# 3_CAN.net
KiCad netlist of a schematic drawn in Altium Designer
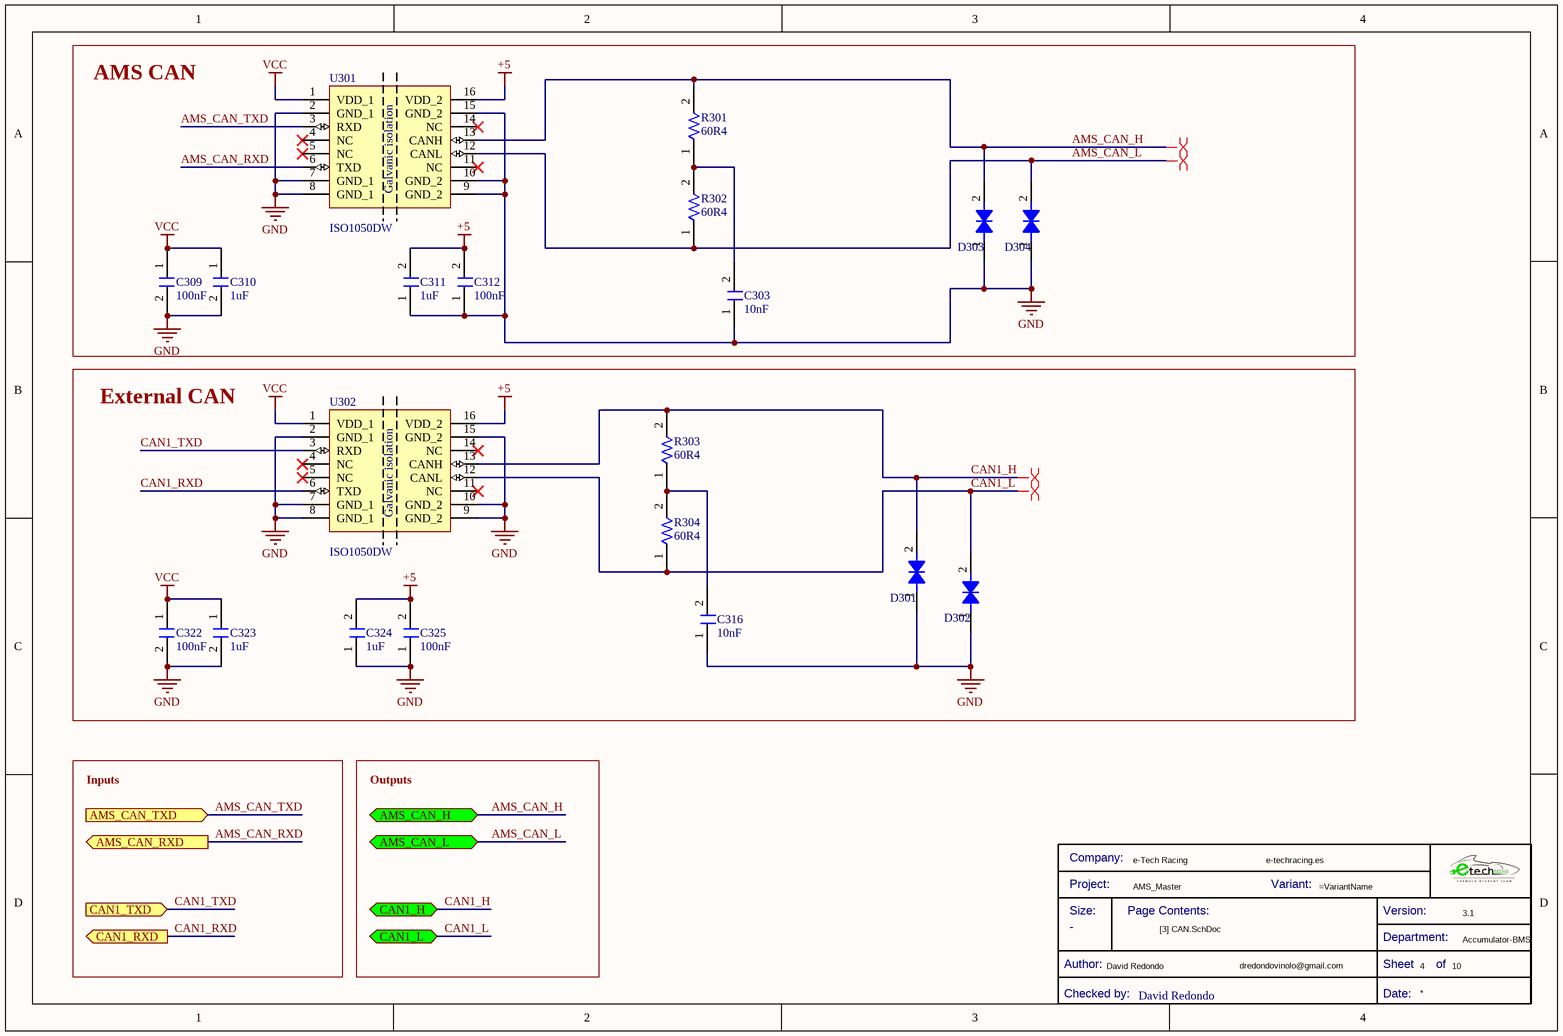
[diagram p0: [3] CAN.SchDoc]

(export (version "E")
  (design (tool "Eeschema 10.0.6"))
  (components
    (comp (ref "C303")
      (value "885012207092")
      (footprint "C0805FNPC-R")
      (description "Cap, 0.01ΜF, 50V, 10%, X7R, 0805")
      (fields
        (field (name "TOLERANCE") "10%")
        (field (name "CAPACITANCE") "10nF")
        (field (name ".CREATOR") "DR")
      )
      (libsource (lib "Passives") (part "C10n-50V-0805FNPC-X7R"))
    )
    (comp (ref "C309")
      (value "885012207098")
      (footprint "C0805FNPC-R")
      (description "Cap, 0.1ΜF, 50V, 10%, X7R, 0805")
      (fields
        (field (name "TOLERANCE") "10%")
        (field (name "CAPACITANCE") "100nF")
        (field (name ".CREATOR") "DR")
      )
      (libsource (lib "Passives") (part "C100n-50V-0805FNPC-X7R"))
    )
    (comp (ref "C310")
      (value "885012207103")
      (footprint "C0805FNPC-R")
      (fields
        (field (name "TOLERANCE") "10%")
        (field (name "CAPACITANCE") "1uF")
        (field (name ".CREATOR") "GP")
      )
      (libsource (lib "Passives") (part "C1u-50V-0805FNPC-X7R"))
    )
    (comp (ref "C311")
      (value "885012207103")
      (footprint "C0805FNPC-R")
      (fields
        (field (name "TOLERANCE") "10%")
        (field (name "CAPACITANCE") "1uF")
        (field (name ".CREATOR") "GP")
      )
      (libsource (lib "Passives") (part "C1u-50V-0805FNPC-X7R"))
    )
    (comp (ref "C312")
      (value "885012207098")
      (footprint "C0805FNPC-R")
      (description "Cap, 0.1ΜF, 50V, 10%, X7R, 0805")
      (fields
        (field (name "TOLERANCE") "10%")
        (field (name "CAPACITANCE") "100nF")
        (field (name ".CREATOR") "DR")
      )
      (libsource (lib "Passives") (part "C100n-50V-0805FNPC-X7R"))
    )
    (comp (ref "C316")
      (value "885012207092")
      (footprint "C0805FNPC-R")
      (description "Cap, 0.01ΜF, 50V, 10%, X7R, 0805")
      (fields
        (field (name "TOLERANCE") "10%")
        (field (name "CAPACITANCE") "10nF")
        (field (name ".CREATOR") "DR")
      )
      (libsource (lib "Passives") (part "C10n-50V-0805FNPC-X7R"))
    )
    (comp (ref "C322")
      (value "885012207098")
      (footprint "C0805FNPC-R")
      (description "Cap, 0.1ΜF, 50V, 10%, X7R, 0805")
      (fields
        (field (name "TOLERANCE") "10%")
        (field (name "CAPACITANCE") "100nF")
        (field (name ".CREATOR") "DR")
      )
      (libsource (lib "Passives") (part "C100n-50V-0805FNPC-X7R"))
    )
    (comp (ref "C323")
      (value "885012207103")
      (footprint "C0805FNPC-R")
      (fields
        (field (name "TOLERANCE") "10%")
        (field (name "CAPACITANCE") "1uF")
        (field (name ".CREATOR") "GP")
      )
      (libsource (lib "Passives") (part "C1u-50V-0805FNPC-X7R"))
    )
    (comp (ref "C324")
      (value "885012207103")
      (footprint "C0805FNPC-R")
      (fields
        (field (name "TOLERANCE") "10%")
        (field (name "CAPACITANCE") "1uF")
        (field (name ".CREATOR") "GP")
      )
      (libsource (lib "Passives") (part "C1u-50V-0805FNPC-X7R"))
    )
    (comp (ref "C325")
      (value "885012207098")
      (footprint "C0805FNPC-R")
      (description "Cap, 0.1ΜF, 50V, 10%, X7R, 0805")
      (fields
        (field (name "TOLERANCE") "10%")
        (field (name "CAPACITANCE") "100nF")
        (field (name ".CREATOR") "DR")
      )
      (libsource (lib "Passives") (part "C100n-50V-0805FNPC-X7R"))
    )
    (comp (ref "D301")
      (value "824501600")
      (footprint "DTVS-DO-214AC")
      (description "TVS diode [Würth Elektronik] 824501600 TVS diode")
      (fields (field (name "MANUFACTURER") "Wurth Electronics") (field (name ".CREATOR") "DO"))
      (libsource (lib "Filter components") (part "DTVS-6V-DO-214AC"))
    )
    (comp (ref "D302")
      (value "824501600")
      (footprint "DTVS-DO-214AC")
      (description "TVS diode [Würth Elektronik] 824501600 TVS diode")
      (fields (field (name "MANUFACTURER") "Wurth Electronics") (field (name ".CREATOR") "DO"))
      (libsource (lib "Filter components") (part "DTVS-6V-DO-214AC"))
    )
    (comp (ref "D303")
      (value "824501600")
      (footprint "DTVS-DO-214AC")
      (description "TVS diode [Würth Elektronik] 824501600 TVS diode")
      (fields (field (name "MANUFACTURER") "Wurth Electronics") (field (name ".CREATOR") "DO"))
      (libsource (lib "Filter components") (part "DTVS-6V-DO-214AC"))
    )
    (comp (ref "D304")
      (value "824501600")
      (footprint "DTVS-DO-214AC")
      (description "TVS diode [Würth Elektronik] 824501600 TVS diode")
      (fields (field (name "MANUFACTURER") "Wurth Electronics") (field (name ".CREATOR") "DO"))
      (libsource (lib "Filter components") (part "DTVS-6V-DO-214AC"))
    )
    (comp (ref "R301")
      (value "60R4")
      (footprint "R0805FTK")
      (description "Res Thin Film 0805 60.4 Ohm 0.1% 1/8W ±25ppm/°C Molded SMD SMD Punched Carrier T/R")
      (fields
        (field (name "TOLERANCE") "0.1%")
        (field (name "Comment") "R60-0805FTN")
        (field (name ".CREATOR") "DR")
      )
      (libsource (lib "Passives") (part "R60-0805FTN"))
    )
    (comp (ref "R302")
      (value "60R4")
      (footprint "R0805FTK")
      (description "Res Thin Film 0805 60.4 Ohm 0.1% 1/8W ±25ppm/°C Molded SMD SMD Punched Carrier T/R")
      (fields
        (field (name "TOLERANCE") "0.1%")
        (field (name "Comment") "R60-0805FTN")
        (field (name ".CREATOR") "DR")
      )
      (libsource (lib "Passives") (part "R60-0805FTN"))
    )
    (comp (ref "R303")
      (value "60R4")
      (footprint "R0805FTK")
      (description "Res Thin Film 0805 60.4 Ohm 0.1% 1/8W ±25ppm/°C Molded SMD SMD Punched Carrier T/R")
      (fields
        (field (name "TOLERANCE") "0.1%")
        (field (name "Comment") "R60-0805FTN")
        (field (name ".CREATOR") "DR")
      )
      (libsource (lib "Passives") (part "R60-0805FTN"))
    )
    (comp (ref "R304")
      (value "60R4")
      (footprint "R0805FTK")
      (description "Res Thin Film 0805 60.4 Ohm 0.1% 1/8W ±25ppm/°C Molded SMD SMD Punched Carrier T/R")
      (fields
        (field (name "TOLERANCE") "0.1%")
        (field (name "Comment") "R60-0805FTN")
        (field (name ".CREATOR") "DR")
      )
      (libsource (lib "Passives") (part "R60-0805FTN"))
    )
    (comp (ref "U301")
      (value "ISO1050DW")
      (footprint "TRANSCEIVER_CAN_SOIC16")
      (description "Isolated 5-V CAN transceiver 16-SOIC -55 to 105")
      (fields (field (name "SUPPLIER PART NUMBER 1") "ISO1050DW") (field (name ".CREATOR") "DR"))
      (libsource (lib "Integrated circuits") (part "Transceiver_CAN_ISO1050"))
    )
    (comp (ref "U302")
      (value "ISO1050DW")
      (footprint "TRANSCEIVER_CAN_SOIC16")
      (description "Isolated 5-V CAN transceiver 16-SOIC -55 to 105")
      (fields (field (name "SUPPLIER PART NUMBER 1") "ISO1050DW") (field (name ".CREATOR") "DR"))
      (libsource (lib "Integrated circuits") (part "Transceiver_CAN_ISO1050"))
    )
  )
  (nets
    (net (code "1") (name "+5") (class "Default")
      (node (ref "C311") (pin "2") (pinfunction "2_2") (pintype "passive"))
      (node (ref "C312") (pin "2") (pinfunction "2_2") (pintype "passive"))
      (node (ref "C324") (pin "2") (pinfunction "2_2") (pintype "passive"))
      (node (ref "C325") (pin "2") (pinfunction "2_2") (pintype "passive"))
      (node (ref "U301") (pin "16") (pinfunction "VDD_2_16") (pintype "passive"))
      (node (ref "U302") (pin "16") (pinfunction "VDD_2_16") (pintype "passive"))
    )
    (net (code "2") (name "/AMS_CAN_H") (class "Default")
      (node (ref "D303") (pin "2") (pinfunction "2_2") (pintype "passive"))
      (node (ref "R301") (pin "2") (pinfunction "2_2") (pintype "passive"))
      (node (ref "U301") (pin "13") (pinfunction "CANH_13") (pintype "bidirectional"))
    )
    (net (code "3") (name "/AMS_CAN_L") (class "Default")
      (node (ref "D304") (pin "2") (pinfunction "2_2") (pintype "passive"))
      (node (ref "R302") (pin "1") (pinfunction "1_1") (pintype "passive"))
      (node (ref "U301") (pin "12") (pinfunction "CANL_12") (pintype "bidirectional"))
    )
    (net (code "4") (name "/AMS_CAN_RXD") (class "Default")
      (node (ref "U301") (pin "6") (pinfunction "TXD_6") (pintype "bidirectional"))
    )
    (net (code "5") (name "/AMS_CAN_TXD") (class "Default")
      (node (ref "U301") (pin "3") (pinfunction "RXD_3") (pintype "bidirectional"))
    )
    (net (code "6") (name "/CAN1_H") (class "Default")
      (node (ref "D301") (pin "2") (pinfunction "2_2") (pintype "passive"))
      (node (ref "R303") (pin "2") (pinfunction "2_2") (pintype "passive"))
      (node (ref "U302") (pin "13") (pinfunction "CANH_13") (pintype "bidirectional"))
    )
    (net (code "7") (name "/CAN1_L") (class "Default")
      (node (ref "D302") (pin "2") (pinfunction "2_2") (pintype "passive"))
      (node (ref "R304") (pin "1") (pinfunction "1_1") (pintype "passive"))
      (node (ref "U302") (pin "12") (pinfunction "CANL_12") (pintype "bidirectional"))
    )
    (net (code "8") (name "/CAN1_RXD") (class "Default")
      (node (ref "U302") (pin "6") (pinfunction "TXD_6") (pintype "bidirectional"))
    )
    (net (code "9") (name "/CAN1_TXD") (class "Default")
      (node (ref "U302") (pin "3") (pinfunction "RXD_3") (pintype "bidirectional"))
    )
    (net (code "10") (name "GND") (class "Default")
      (node (ref "C303") (pin "1") (pinfunction "1_1") (pintype "passive"))
      (node (ref "C309") (pin "2") (pinfunction "2_2") (pintype "passive"))
      (node (ref "C310") (pin "2") (pinfunction "2_2") (pintype "passive"))
      (node (ref "C311") (pin "1") (pinfunction "1_1") (pintype "passive"))
      (node (ref "C312") (pin "1") (pinfunction "1_1") (pintype "passive"))
      (node (ref "C316") (pin "1") (pinfunction "1_1") (pintype "passive"))
      (node (ref "C322") (pin "2") (pinfunction "2_2") (pintype "passive"))
      (node (ref "C323") (pin "2") (pinfunction "2_2") (pintype "passive"))
      (node (ref "C324") (pin "1") (pinfunction "1_1") (pintype "passive"))
      (node (ref "C325") (pin "1") (pinfunction "1_1") (pintype "passive"))
      (node (ref "D301") (pin "1") (pinfunction "1_1") (pintype "passive"))
      (node (ref "D302") (pin "1") (pinfunction "1_1") (pintype "passive"))
      (node (ref "D303") (pin "1") (pinfunction "1_1") (pintype "passive"))
      (node (ref "D304") (pin "1") (pinfunction "1_1") (pintype "passive"))
      (node (ref "U301") (pin "10") (pinfunction "GND_2_10") (pintype "passive"))
      (node (ref "U301") (pin "15") (pinfunction "GND_2_15") (pintype "passive"))
      (node (ref "U301") (pin "2") (pinfunction "GND_1_2") (pintype "power_in"))
      (node (ref "U301") (pin "7") (pinfunction "GND_1_7") (pintype "passive"))
      (node (ref "U301") (pin "8") (pinfunction "GND_1_8") (pintype "passive"))
      (node (ref "U301") (pin "9") (pinfunction "GND_2_9") (pintype "passive"))
      (node (ref "U302") (pin "10") (pinfunction "GND_2_10") (pintype "passive"))
      (node (ref "U302") (pin "15") (pinfunction "GND_2_15") (pintype "passive"))
      (node (ref "U302") (pin "2") (pinfunction "GND_1_2") (pintype "power_in"))
      (node (ref "U302") (pin "7") (pinfunction "GND_1_7") (pintype "passive"))
      (node (ref "U302") (pin "8") (pinfunction "GND_1_8") (pintype "passive"))
      (node (ref "U302") (pin "9") (pinfunction "GND_2_9") (pintype "passive"))
    )
    (net (code "11") (name "Net-(C303-Pad2)") (class "Default")
      (node (ref "C303") (pin "2") (pinfunction "2_2") (pintype "passive"))
      (node (ref "R301") (pin "1") (pinfunction "1_1") (pintype "passive"))
      (node (ref "R302") (pin "2") (pinfunction "2_2") (pintype "passive"))
    )
    (net (code "12") (name "Net-(C316-Pad2)") (class "Default")
      (node (ref "C316") (pin "2") (pinfunction "2_2") (pintype "passive"))
      (node (ref "R303") (pin "1") (pinfunction "1_1") (pintype "passive"))
      (node (ref "R304") (pin "2") (pinfunction "2_2") (pintype "passive"))
    )
    (net (code "13") (name "VCC") (class "Default")
      (node (ref "C309") (pin "1") (pinfunction "1_1") (pintype "passive"))
      (node (ref "C310") (pin "1") (pinfunction "1_1") (pintype "passive"))
      (node (ref "C322") (pin "1") (pinfunction "1_1") (pintype "passive"))
      (node (ref "C323") (pin "1") (pinfunction "1_1") (pintype "passive"))
      (node (ref "U301") (pin "1") (pinfunction "VDD_1_1") (pintype "open_collector"))
      (node (ref "U302") (pin "1") (pinfunction "VDD_1_1") (pintype "open_collector"))
    )
    (net (code "14") (name "unconnected-(U301-NC-Pad4)") (class "Default")
      (node (ref "U301") (pin "4") (pinfunction "NC_4") (pintype "open_emitter+no_connect"))
    )
    (net (code "15") (name "unconnected-(U301-NC-Pad5)") (class "Default")
      (node (ref "U301") (pin "5") (pinfunction "NC_5") (pintype "passive+no_connect"))
    )
    (net (code "16") (name "unconnected-(U301-NC-Pad11)") (class "Default")
      (node (ref "U301") (pin "11") (pinfunction "NC_11") (pintype "passive+no_connect"))
    )
    (net (code "17") (name "unconnected-(U301-NC-Pad14)") (class "Default")
      (node (ref "U301") (pin "14") (pinfunction "NC_14") (pintype "open_collector+no_connect"))
    )
    (net (code "18") (name "unconnected-(U302-NC-Pad4)") (class "Default")
      (node (ref "U302") (pin "4") (pinfunction "NC_4") (pintype "open_emitter+no_connect"))
    )
    (net (code "19") (name "unconnected-(U302-NC-Pad5)") (class "Default")
      (node (ref "U302") (pin "5") (pinfunction "NC_5") (pintype "passive+no_connect"))
    )
    (net (code "20") (name "unconnected-(U302-NC-Pad11)") (class "Default")
      (node (ref "U302") (pin "11") (pinfunction "NC_11") (pintype "passive+no_connect"))
    )
    (net (code "21") (name "unconnected-(U302-NC-Pad14)") (class "Default")
      (node (ref "U302") (pin "14") (pinfunction "NC_14") (pintype "open_collector+no_connect"))
    )
  )
)
